# V2.net
KiCad netlist of a schematic drawn in EAGLE
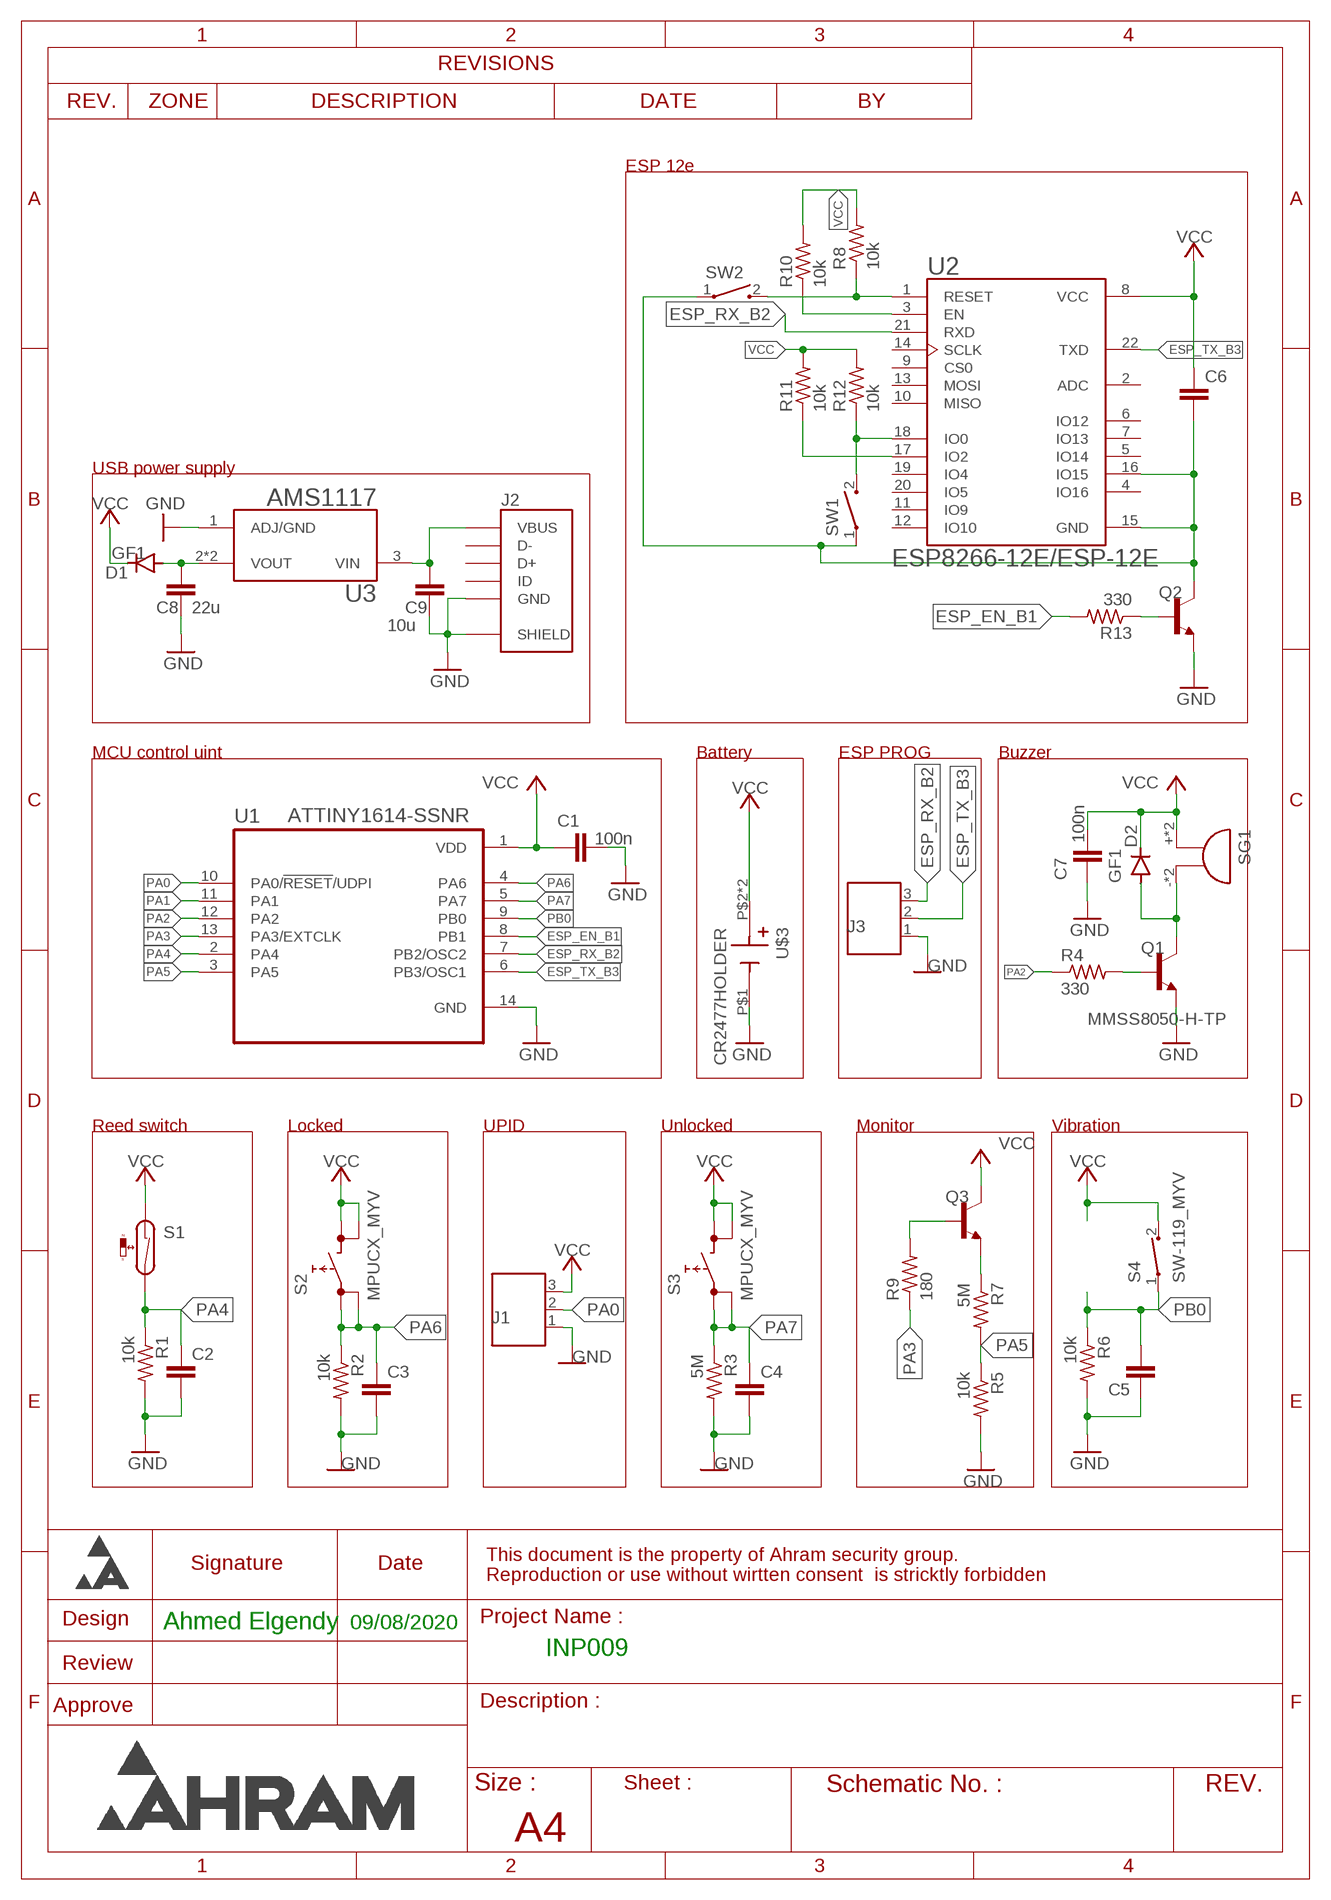
[diagram p0: schematic, sheet 1]

(export (version "E")
  (design (tool "Eeschema 10.0.6"))
  (components
    (comp (ref "C1")
      (value "100n")
      (footprint "eagle-import:C0805K")
      (libsource (lib "eagle-import") (part "C-EUC0805K"))
    )
    (comp (ref "C2")
      (value "C-EUC0805K")
      (footprint "eagle-import:C0805K")
      (libsource (lib "eagle-import") (part "C-EUC0805K"))
    )
    (comp (ref "C3")
      (value "C-EUC0805K")
      (footprint "eagle-import:C0805K")
      (libsource (lib "eagle-import") (part "C-EUC0805K"))
    )
    (comp (ref "C4")
      (value "C-EUC0805K")
      (footprint "eagle-import:C0805K")
      (libsource (lib "eagle-import") (part "C-EUC0805K"))
    )
    (comp (ref "C5")
      (value "C-EUC0805K")
      (footprint "eagle-import:C0805K")
      (libsource (lib "eagle-import") (part "C-EUC0805K"))
    )
    (comp (ref "C6")
      (value "C-EUC0805K")
      (footprint "eagle-import:C0805K")
      (libsource (lib "eagle-import") (part "C-EUC0805K"))
    )
    (comp (ref "C7")
      (value "100n")
      (footprint "eagle-import:C0805K")
      (libsource (lib "eagle-import") (part "C-EUC0805K"))
    )
    (comp (ref "C8")
      (value "22u")
      (footprint "eagle-import:C0805K")
      (libsource (lib "eagle-import") (part "C-EUC0805K"))
    )
    (comp (ref "C9")
      (value "10u")
      (footprint "eagle-import:C0805K")
      (libsource (lib "eagle-import") (part "C-EUC0805K"))
    )
    (comp (ref "D1")
      (value "GF1")
      (footprint "eagle-import:SMA-DO214AC")
      (libsource (lib "eagle-import") (part "GF1"))
    )
    (comp (ref "D2")
      (value "GF1")
      (footprint "eagle-import:SMA-DO214AC")
      (libsource (lib "eagle-import") (part "GF1"))
    )
    (comp (ref "J1")
      (value "691508110303")
      (footprint "eagle-import:691508110303")
      (libsource (lib "eagle-import") (part "691508110303"))
    )
    (comp (ref "J2")
      (value "USB3065-XX-00-A_REVE")
      (footprint "eagle-import:GCT_USB3065-XX-00-A_REVE")
      (fields (field (name "MF") "Global Connector Technology") (field (name "MP") "USB3065-30-00-A"))
      (libsource (lib "eagle-import") (part "USB3065-XX-00-A_REVE"))
    )
    (comp (ref "J3")
      (value "691508110303")
      (footprint "eagle-import:691508110303")
      (libsource (lib "eagle-import") (part "691508110303"))
    )
    (comp (ref "Q1")
      (value "MMSS8050-H-TP")
      (footprint "eagle-import:TRANS_MMSS8050-H-TP")
      (fields (field (name "MF") "Micro Commercial"))
      (libsource (lib "eagle-import") (part "MMSS8050-H-TP"))
    )
    (comp (ref "Q2")
      (value "MMSS8050-H-TP")
      (footprint "eagle-import:TRANS_MMSS8050-H-TP")
      (fields (field (name "MF") "Micro Commercial"))
      (libsource (lib "eagle-import") (part "MMSS8050-H-TP"))
    )
    (comp (ref "Q3")
      (value "MMSS8050-H-TP")
      (footprint "eagle-import:TRANS_MMSS8050-H-TP")
      (fields (field (name "MF") "Micro Commercial"))
      (libsource (lib "eagle-import") (part "MMSS8050-H-TP"))
    )
    (comp (ref "R1")
      (value "10k")
      (footprint "eagle-import:M0805")
      (libsource (lib "eagle-import") (part "R-US_M0805"))
    )
    (comp (ref "R2")
      (value "10k")
      (footprint "eagle-import:M0805")
      (libsource (lib "eagle-import") (part "R-US_M0805"))
    )
    (comp (ref "R3")
      (value "5M")
      (footprint "eagle-import:M0805")
      (libsource (lib "eagle-import") (part "R-US_M0805"))
    )
    (comp (ref "R4")
      (value "330")
      (footprint "eagle-import:M0805")
      (libsource (lib "eagle-import") (part "R-US_M0805"))
    )
    (comp (ref "R5")
      (value "10k")
      (footprint "eagle-import:M0805")
      (libsource (lib "eagle-import") (part "R-US_M0805"))
    )
    (comp (ref "R6")
      (value "10k")
      (footprint "eagle-import:M0805")
      (libsource (lib "eagle-import") (part "R-US_M0805"))
    )
    (comp (ref "R7")
      (value "5M")
      (footprint "eagle-import:M0805")
      (libsource (lib "eagle-import") (part "R-US_M0805"))
    )
    (comp (ref "R8")
      (value "10k")
      (footprint "eagle-import:M0805")
      (libsource (lib "eagle-import") (part "R-US_M0805"))
    )
    (comp (ref "R9")
      (value "180")
      (footprint "eagle-import:M0805")
      (libsource (lib "eagle-import") (part "R-US_M0805"))
    )
    (comp (ref "R10")
      (value "10k")
      (footprint "eagle-import:M0805")
      (libsource (lib "eagle-import") (part "R-US_M0805"))
    )
    (comp (ref "R11")
      (value "10k")
      (footprint "eagle-import:M0805")
      (libsource (lib "eagle-import") (part "R-US_M0805"))
    )
    (comp (ref "R12")
      (value "10k")
      (footprint "eagle-import:M0805")
      (libsource (lib "eagle-import") (part "R-US_M0805"))
    )
    (comp (ref "R13")
      (value "330")
      (footprint "eagle-import:M0805")
      (libsource (lib "eagle-import") (part "R-US_M0805"))
    )
    (comp (ref "S1")
      (value "RI80SMDM-MYV")
      (footprint "eagle-import:RI80SMDM-0510-J1")
      (libsource (lib "eagle-import") (part "RI80SMDM-MYV"))
    )
    (comp (ref "S2")
      (value "MPUCX_MYV")
      (footprint "eagle-import:MPUCX_MYV")
      (libsource (lib "eagle-import") (part "MPUCX_MYV"))
    )
    (comp (ref "S3")
      (value "MPUCX_MYV")
      (footprint "eagle-import:MPUCX_MYV")
      (libsource (lib "eagle-import") (part "MPUCX_MYV"))
    )
    (comp (ref "S4")
      (value "SW-119_MYV")
      (footprint "eagle-import:SW-119")
      (libsource (lib "eagle-import") (part "SW-119_MYV"))
    )
    (comp (ref "SG1")
      (value "CMI-9653S-SMT")
      (footprint "eagle-import:SMD_BUZZER")
      (libsource (lib "eagle-import") (part "CMI-9653S-SMT"))
    )
    (comp (ref "SW1")
      (value "1437566-3")
      (footprint "eagle-import:SW_1437566-3")
      (fields (field (name "MF") "TE Connectivity"))
      (libsource (lib "eagle-import") (part "1437566-3"))
    )
    (comp (ref "SW2")
      (value "1437566-3")
      (footprint "eagle-import:SW_1437566-3")
      (fields (field (name "MF") "TE Connectivity"))
      (libsource (lib "eagle-import") (part "1437566-3"))
    )
    (comp (ref "U$3")
      (value "CR2477HOLDER")
      (footprint "eagle-import:CR2477")
      (libsource (lib "eagle-import") (part "CR2477HOLDER"))
    )
    (comp (ref "U1")
      (value "ATTINY1614-SSNR")
      (footprint "eagle-import:SOIC127P600X175-14N")
      (fields (field (name "MF") "Microchip Technology"))
      (libsource (lib "eagle-import") (part "ATTINY1614-SSNR"))
    )
    (comp (ref "U2")
      (value "ESP8266-12E/ESP-12E")
      (footprint "eagle-import:XCVR_ESP8266-12E_ESP-12E")
      (fields (field (name "MF") "AI-Thinker"))
      (libsource (lib "eagle-import") (part "ESP8266-12E/ESP-12E"))
    )
    (comp (ref "U3")
      (value "AMS1117")
      (footprint "eagle-import:SOT229P700X180-4N")
      (fields (field (name "MF") "Seeed Technology"))
      (libsource (lib "eagle-import") (part "AMS1117"))
    )
  )
  (nets
    (net (code "1") (name "ESP_EN_B1") (class "Default")
      (node (ref "R13") (pin "2") (pinfunction "2_2") (pintype "passive"))
      (node (ref "U1") (pin "8") (pinfunction "PB1_8") (pintype "bidirectional"))
    )
    (net (code "2") (name "ESP_RX_B2") (class "Default")
      (node (ref "J3") (pin "3") (pinfunction "3_3") (pintype "passive"))
      (node (ref "U1") (pin "7") (pinfunction "PB2/OSC2_7") (pintype "bidirectional"))
      (node (ref "U2") (pin "21") (pinfunction "RXD_21") (pintype "input"))
    )
    (net (code "3") (name "ESP_TX_B3") (class "Default")
      (node (ref "J3") (pin "2") (pinfunction "2_2") (pintype "passive"))
      (node (ref "U1") (pin "6") (pinfunction "PB3/OSC1_6") (pintype "bidirectional"))
      (node (ref "U2") (pin "22") (pinfunction "TXD_22") (pintype "output"))
    )
    (net (code "4") (name "GND") (class "Default")
      (node (ref "C1") (pin "2") (pinfunction "2_2") (pintype "passive"))
      (node (ref "C2") (pin "2") (pinfunction "2_2") (pintype "passive"))
      (node (ref "C3") (pin "2") (pinfunction "2_2") (pintype "passive"))
      (node (ref "C4") (pin "2") (pinfunction "2_2") (pintype "passive"))
      (node (ref "C5") (pin "1") (pinfunction "1_1") (pintype "passive"))
      (node (ref "C7") (pin "1") (pinfunction "1_1") (pintype "passive"))
      (node (ref "C8") (pin "1") (pinfunction "1_1") (pintype "passive"))
      (node (ref "C9") (pin "1") (pinfunction "1_1") (pintype "passive"))
      (node (ref "J1") (pin "1") (pinfunction "1_1") (pintype "passive"))
      (node (ref "J2") (pin "5") (pinfunction "GND_5") (pintype "power_in"))
      (node (ref "J2") (pin "6") (pinfunction "SHIELD_6") (pintype "power_in"))
      (node (ref "J2") (pin "7") (pinfunction "SHIELD_7") (pintype "power_in"))
      (node (ref "J2") (pin "8") (pinfunction "SHIELD_8") (pintype "power_in"))
      (node (ref "J2") (pin "9") (pinfunction "SHIELD_9") (pintype "power_in"))
      (node (ref "J3") (pin "1") (pinfunction "1_1") (pintype "passive"))
      (node (ref "Q1") (pin "2") (pinfunction "E_2") (pintype "passive"))
      (node (ref "Q2") (pin "2") (pinfunction "E_2") (pintype "passive"))
      (node (ref "R1") (pin "2") (pinfunction "2_2") (pintype "passive"))
      (node (ref "R2") (pin "2") (pinfunction "2_2") (pintype "passive"))
      (node (ref "R3") (pin "2") (pinfunction "2_2") (pintype "passive"))
      (node (ref "R5") (pin "2") (pinfunction "2_2") (pintype "passive"))
      (node (ref "R6") (pin "2") (pinfunction "2_2") (pintype "passive"))
      (node (ref "U$3") (pin "P$1") (pinfunction "-_P$1") (pintype "passive"))
      (node (ref "U1") (pin "14") (pinfunction "GND_14") (pintype "power_in"))
      (node (ref "U3") (pin "1") (pinfunction "ADJ/GND_1") (pintype "power_in"))
    )
    (net (code "5") (name "Net-(C8-Pad2)") (class "Default")
      (node (ref "C8") (pin "2") (pinfunction "2_2") (pintype "passive"))
      (node (ref "D1") (pin "A") (pinfunction "A_A") (pintype "passive"))
      (node (ref "U3") (pin "2") (pinfunction "VOUT_2") (pintype "output"))
      (node (ref "U3") (pin "4") (pinfunction "VOUT_4") (pintype "output"))
    )
    (net (code "6") (name "Net-(J2-VBUS)") (class "Default")
      (node (ref "C9") (pin "2") (pinfunction "2_2") (pintype "passive"))
      (node (ref "J2") (pin "1") (pinfunction "VBUS_1") (pintype "power_in"))
      (node (ref "U3") (pin "3") (pinfunction "VIN_3") (pintype "input"))
    )
    (net (code "7") (name "Net-(Q1-B)") (class "Default")
      (node (ref "Q1") (pin "1") (pinfunction "B_1") (pintype "passive"))
      (node (ref "R4") (pin "2") (pinfunction "2_2") (pintype "passive"))
    )
    (net (code "8") (name "Net-(Q1-C)") (class "Default")
      (node (ref "D2") (pin "A") (pinfunction "A_A") (pintype "passive"))
      (node (ref "Q1") (pin "3") (pinfunction "C_3") (pintype "passive"))
      (node (ref "SG1") (pin "-") (pinfunction "-_-") (pintype "passive"))
      (node (ref "SG1") (pin "--") (pinfunction "-_--") (pintype "passive"))
    )
    (net (code "9") (name "Net-(Q2-B)") (class "Default")
      (node (ref "Q2") (pin "1") (pinfunction "B_1") (pintype "passive"))
      (node (ref "R13") (pin "1") (pinfunction "1_1") (pintype "passive"))
    )
    (net (code "10") (name "Net-(Q2-C)") (class "Default")
      (node (ref "C6") (pin "2") (pinfunction "2_2") (pintype "passive"))
      (node (ref "Q2") (pin "3") (pinfunction "C_3") (pintype "passive"))
      (node (ref "SW1") (pin "1") (pinfunction "1_1") (pintype "passive"))
      (node (ref "SW2") (pin "1") (pinfunction "1_1") (pintype "passive"))
      (node (ref "U2") (pin "15") (pinfunction "GND_15") (pintype "power_in"))
      (node (ref "U2") (pin "16") (pinfunction "IO15_16") (pintype "bidirectional"))
    )
    (net (code "11") (name "Net-(Q3-B)") (class "Default")
      (node (ref "Q3") (pin "1") (pinfunction "B_1") (pintype "passive"))
      (node (ref "R9") (pin "2") (pinfunction "2_2") (pintype "passive"))
    )
    (net (code "12") (name "Net-(Q3-E)") (class "Default")
      (node (ref "Q3") (pin "2") (pinfunction "E_2") (pintype "passive"))
      (node (ref "R7") (pin "1") (pinfunction "1_1") (pintype "passive"))
    )
    (net (code "13") (name "Net-(U2-EN)") (class "Default")
      (node (ref "R10") (pin "1") (pinfunction "1_1") (pintype "passive"))
      (node (ref "U2") (pin "3") (pinfunction "EN_3") (pintype "input"))
    )
    (net (code "14") (name "Net-(U2-IO0)") (class "Default")
      (node (ref "R12") (pin "1") (pinfunction "1_1") (pintype "passive"))
      (node (ref "SW1") (pin "2") (pinfunction "2_2") (pintype "passive"))
      (node (ref "U2") (pin "18") (pinfunction "IO0_18") (pintype "bidirectional"))
    )
    (net (code "15") (name "Net-(U2-IO2)") (class "Default")
      (node (ref "R11") (pin "1") (pinfunction "1_1") (pintype "passive"))
      (node (ref "U2") (pin "17") (pinfunction "IO2_17") (pintype "bidirectional"))
    )
    (net (code "16") (name "Net-(U2-RESET)") (class "Default")
      (node (ref "R8") (pin "1") (pinfunction "1_1") (pintype "passive"))
      (node (ref "SW2") (pin "2") (pinfunction "2_2") (pintype "passive"))
      (node (ref "U2") (pin "1") (pinfunction "RESET_1") (pintype "input"))
    )
    (net (code "17") (name "PA0") (class "Default")
      (node (ref "J1") (pin "2") (pinfunction "2_2") (pintype "passive"))
      (node (ref "U1") (pin "10") (pinfunction "PA0/~{RESET}/UDPI_10") (pintype "bidirectional"))
    )
    (net (code "18") (name "PA1") (class "Default")
      (node (ref "U1") (pin "11") (pinfunction "PA1_11") (pintype "bidirectional"))
    )
    (net (code "19") (name "PA2") (class "Default")
      (node (ref "R4") (pin "1") (pinfunction "1_1") (pintype "passive"))
      (node (ref "U1") (pin "12") (pinfunction "PA2_12") (pintype "bidirectional"))
    )
    (net (code "20") (name "PA3") (class "Default")
      (node (ref "R9") (pin "1") (pinfunction "1_1") (pintype "passive"))
      (node (ref "U1") (pin "13") (pinfunction "PA3/EXTCLK_13") (pintype "bidirectional"))
    )
    (net (code "21") (name "PA4") (class "Default")
      (node (ref "C2") (pin "1") (pinfunction "1_1") (pintype "passive"))
      (node (ref "R1") (pin "1") (pinfunction "1_1") (pintype "passive"))
      (node (ref "S1") (pin "P$2") (pinfunction "2_P$2") (pintype "passive"))
      (node (ref "U1") (pin "2") (pinfunction "PA4_2") (pintype "bidirectional"))
    )
    (net (code "22") (name "PA5") (class "Default")
      (node (ref "R5") (pin "1") (pinfunction "1_1") (pintype "passive"))
      (node (ref "R7") (pin "2") (pinfunction "2_2") (pintype "passive"))
      (node (ref "U1") (pin "3") (pinfunction "PA5_3") (pintype "bidirectional"))
    )
    (net (code "23") (name "PA6") (class "Default")
      (node (ref "C3") (pin "1") (pinfunction "1_1") (pintype "passive"))
      (node (ref "R2") (pin "1") (pinfunction "1_1") (pintype "passive"))
      (node (ref "S2") (pin "1") (pinfunction "1_1") (pintype "passive"))
      (node (ref "S2") (pin "2") (pinfunction "2_2") (pintype "passive"))
      (node (ref "U1") (pin "4") (pinfunction "PA6_4") (pintype "bidirectional"))
    )
    (net (code "24") (name "PA7") (class "Default")
      (node (ref "C4") (pin "1") (pinfunction "1_1") (pintype "passive"))
      (node (ref "R3") (pin "1") (pinfunction "1_1") (pintype "passive"))
      (node (ref "S3") (pin "1") (pinfunction "1_1") (pintype "passive"))
      (node (ref "S3") (pin "2") (pinfunction "2_2") (pintype "passive"))
      (node (ref "U1") (pin "5") (pinfunction "PA7_5") (pintype "bidirectional"))
    )
    (net (code "25") (name "PB0") (class "Default")
      (node (ref "C5") (pin "2") (pinfunction "2_2") (pintype "passive"))
      (node (ref "R6") (pin "1") (pinfunction "1_1") (pintype "passive"))
      (node (ref "S4") (pin "1") (pinfunction "1_1") (pintype "passive"))
      (node (ref "U1") (pin "9") (pinfunction "PB0_9") (pintype "bidirectional"))
    )
    (net (code "26") (name "VCC") (class "Default")
      (node (ref "C1") (pin "1") (pinfunction "1_1") (pintype "passive"))
      (node (ref "C6") (pin "1") (pinfunction "1_1") (pintype "passive"))
      (node (ref "C7") (pin "2") (pinfunction "2_2") (pintype "passive"))
      (node (ref "D1") (pin "K") (pinfunction "C_K") (pintype "passive"))
      (node (ref "D2") (pin "K") (pinfunction "C_K") (pintype "passive"))
      (node (ref "J1") (pin "3") (pinfunction "3_3") (pintype "passive"))
      (node (ref "Q3") (pin "3") (pinfunction "C_3") (pintype "passive"))
      (node (ref "R10") (pin "2") (pinfunction "2_2") (pintype "passive"))
      (node (ref "R11") (pin "2") (pinfunction "2_2") (pintype "passive"))
      (node (ref "R12") (pin "2") (pinfunction "2_2") (pintype "passive"))
      (node (ref "R8") (pin "2") (pinfunction "2_2") (pintype "passive"))
      (node (ref "S1") (pin "P$1") (pinfunction "1_P$1") (pintype "passive"))
      (node (ref "S2") (pin "3") (pinfunction "3_3") (pintype "passive"))
      (node (ref "S2") (pin "4") (pinfunction "4_4") (pintype "passive"))
      (node (ref "S3") (pin "3") (pinfunction "3_3") (pintype "passive"))
      (node (ref "S3") (pin "4") (pinfunction "4_4") (pintype "passive"))
      (node (ref "S4") (pin "2") (pinfunction "2_2") (pintype "passive"))
      (node (ref "SG1") (pin "+") (pinfunction "+_+") (pintype "passive"))
      (node (ref "SG1") (pin "++") (pinfunction "+_++") (pintype "passive"))
      (node (ref "U$3") (pin "P$2") (pinfunction "+_P$2") (pintype "passive"))
      (node (ref "U$3") (pin "P$3") (pinfunction "+_P$3") (pintype "passive"))
      (node (ref "U1") (pin "1") (pinfunction "VDD_1") (pintype "power_in"))
      (node (ref "U2") (pin "8") (pinfunction "VCC_8") (pintype "power_in"))
    )
    (net (code "27") (name "unconnected-(J2-D+-Pad3)") (class "Default")
      (node (ref "J2") (pin "3") (pinfunction "D+_3") (pintype "bidirectional"))
    )
    (net (code "28") (name "unconnected-(J2-D--Pad2)") (class "Default")
      (node (ref "J2") (pin "2") (pinfunction "D-_2") (pintype "bidirectional"))
    )
    (net (code "29") (name "unconnected-(J2-ID-Pad4)") (class "Default")
      (node (ref "J2") (pin "4") (pinfunction "ID_4") (pintype "bidirectional"))
    )
    (net (code "30") (name "unconnected-(U2-ADC-Pad2)") (class "Default")
      (node (ref "U2") (pin "2") (pinfunction "ADC_2") (pintype "passive"))
    )
    (net (code "31") (name "unconnected-(U2-CS0-Pad9)") (class "Default")
      (node (ref "U2") (pin "9") (pinfunction "CS0_9") (pintype "input"))
    )
    (net (code "32") (name "unconnected-(U2-IO4-Pad19)") (class "Default")
      (node (ref "U2") (pin "19") (pinfunction "IO4_19") (pintype "bidirectional"))
    )
    (net (code "33") (name "unconnected-(U2-IO5-Pad20)") (class "Default")
      (node (ref "U2") (pin "20") (pinfunction "IO5_20") (pintype "bidirectional"))
    )
    (net (code "34") (name "unconnected-(U2-IO9-Pad11)") (class "Default")
      (node (ref "U2") (pin "11") (pinfunction "IO9_11") (pintype "bidirectional"))
    )
    (net (code "35") (name "unconnected-(U2-IO10-Pad12)") (class "Default")
      (node (ref "U2") (pin "12") (pinfunction "IO10_12") (pintype "bidirectional"))
    )
    (net (code "36") (name "unconnected-(U2-IO12-Pad6)") (class "Default")
      (node (ref "U2") (pin "6") (pinfunction "IO12_6") (pintype "bidirectional"))
    )
    (net (code "37") (name "unconnected-(U2-IO13-Pad7)") (class "Default")
      (node (ref "U2") (pin "7") (pinfunction "IO13_7") (pintype "bidirectional"))
    )
    (net (code "38") (name "unconnected-(U2-IO14-Pad5)") (class "Default")
      (node (ref "U2") (pin "5") (pinfunction "IO14_5") (pintype "bidirectional"))
    )
    (net (code "39") (name "unconnected-(U2-IO16-Pad4)") (class "Default")
      (node (ref "U2") (pin "4") (pinfunction "IO16_4") (pintype "bidirectional"))
    )
    (net (code "40") (name "unconnected-(U2-MISO-Pad10)") (class "Default")
      (node (ref "U2") (pin "10") (pinfunction "MISO_10") (pintype "bidirectional"))
    )
    (net (code "41") (name "unconnected-(U2-MOSI-Pad13)") (class "Default")
      (node (ref "U2") (pin "13") (pinfunction "MOSI_13") (pintype "bidirectional"))
    )
    (net (code "42") (name "unconnected-(U2-SCLK-Pad14)") (class "Default")
      (node (ref "U2") (pin "14") (pinfunction "SCLK_14") (pintype "input"))
    )
  )
)
